# mainboard.net
KiCad netlist of a schematic drawn in EAGLE
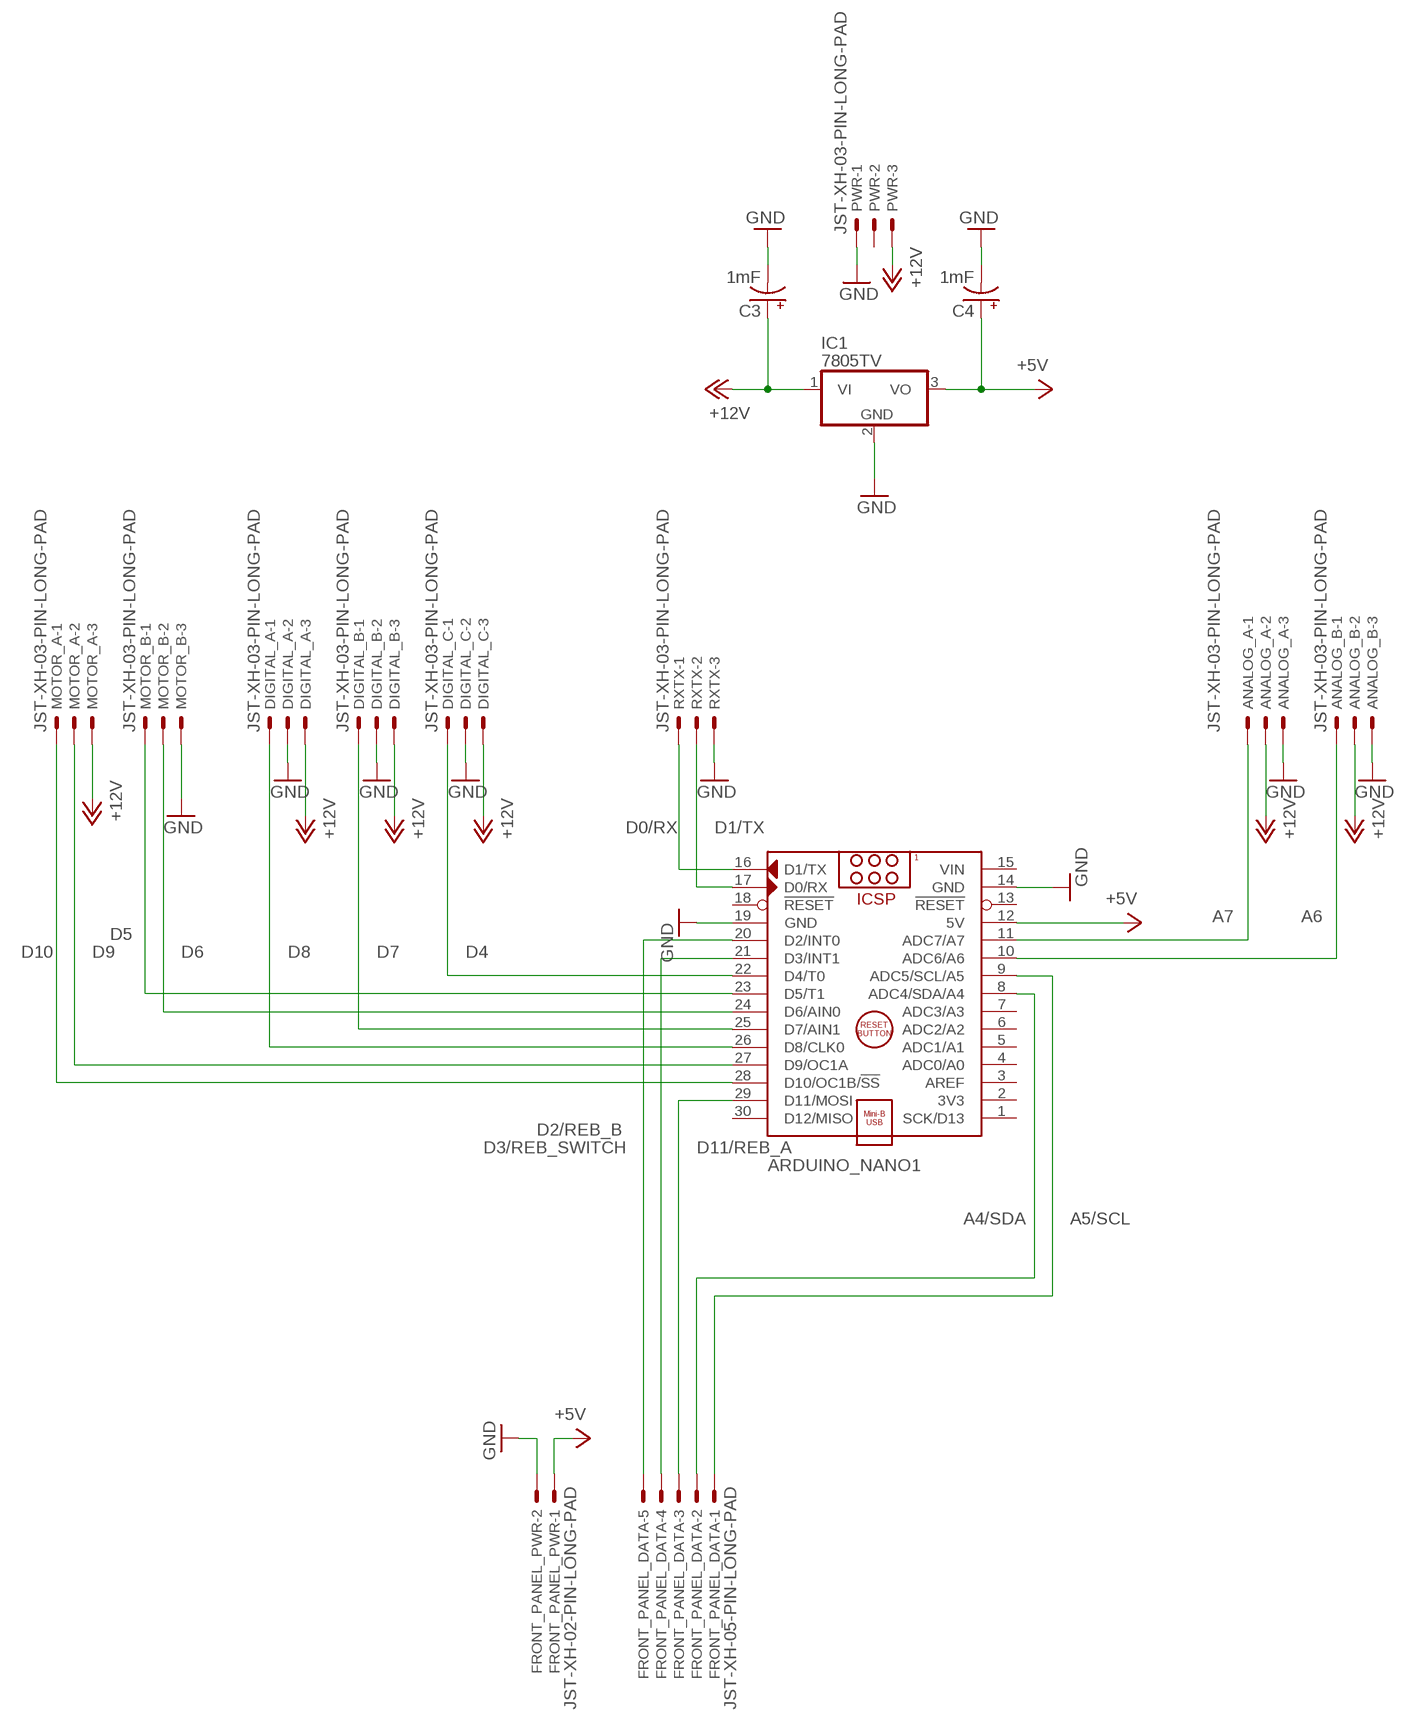
[diagram p0: schematic, sheet 1]

(export (version "E")
  (design (tool "Eeschema 10.0.6"))
  (components
    (comp (ref "ANALOG_A")
      (value "JST-XH-03-PIN-LONG-PAD")
      (footprint "eagle-import:JST-XH-03-PACKAGE-LONG-PAD")
      (libsource (lib "eagle-import") (part "JST-XH-03-PIN-LONG-PAD"))
    )
    (comp (ref "ANALOG_B")
      (value "JST-XH-03-PIN-LONG-PAD")
      (footprint "eagle-import:JST-XH-03-PACKAGE-LONG-PAD")
      (libsource (lib "eagle-import") (part "JST-XH-03-PIN-LONG-PAD"))
    )
    (comp (ref "ARDUINO_NANO1")
      (value "ARDUINO_NANO")
      (footprint "eagle-import:ARDUINO_NANO")
      (libsource (lib "eagle-import") (part "ARDUINO_NANO"))
    )
    (comp (ref "C3")
      (value "1mF")
      (footprint "eagle-import:CPOL-RADIAL-5MM-10MM")
      (libsource (lib "eagle-import") (part "1000UF-RADIAL-5MM-25V-20%"))
    )
    (comp (ref "C4")
      (value "1mF")
      (footprint "eagle-import:CPOL-RADIAL-5MM-10MM")
      (libsource (lib "eagle-import") (part "1000UF-RADIAL-5MM-25V-20%"))
    )
    (comp (ref "DIGITAL_A")
      (value "JST-XH-03-PIN-LONG-PAD")
      (footprint "eagle-import:JST-XH-03-PACKAGE-LONG-PAD")
      (libsource (lib "eagle-import") (part "JST-XH-03-PIN-LONG-PAD"))
    )
    (comp (ref "DIGITAL_B")
      (value "JST-XH-03-PIN-LONG-PAD")
      (footprint "eagle-import:JST-XH-03-PACKAGE-LONG-PAD")
      (libsource (lib "eagle-import") (part "JST-XH-03-PIN-LONG-PAD"))
    )
    (comp (ref "DIGITAL_C")
      (value "JST-XH-03-PIN-LONG-PAD")
      (footprint "eagle-import:JST-XH-03-PACKAGE-LONG-PAD")
      (libsource (lib "eagle-import") (part "JST-XH-03-PIN-LONG-PAD"))
    )
    (comp (ref "FRONT_PANEL_DATA")
      (value "JST-XH-05-PIN-LONG-PAD")
      (footprint "eagle-import:JST-XH-05-PACKAGE-LONG-PAD")
      (libsource (lib "eagle-import") (part "JST-XH-05-PIN-LONG-PAD"))
    )
    (comp (ref "FRONT_PANEL_PWR")
      (value "JST-XH-02-PIN-LONG-PAD")
      (footprint "eagle-import:JST-XH-02-PACKAGE-LONG-PAD")
      (libsource (lib "eagle-import") (part "JST-XH-02-PIN-LONG-PAD"))
    )
    (comp (ref "IC1")
      (value "7805TV")
      (footprint "eagle-import:TO220V")
      (libsource (lib "eagle-import") (part "78TV05"))
    )
    (comp (ref "MOTOR_A")
      (value "JST-XH-03-PIN-LONG-PAD")
      (footprint "eagle-import:JST-XH-03-PACKAGE-LONG-PAD")
      (libsource (lib "eagle-import") (part "JST-XH-03-PIN-LONG-PAD"))
    )
    (comp (ref "MOTOR_B")
      (value "JST-XH-03-PIN-LONG-PAD")
      (footprint "eagle-import:JST-XH-03-PACKAGE-LONG-PAD")
      (libsource (lib "eagle-import") (part "JST-XH-03-PIN-LONG-PAD"))
    )
    (comp (ref "PWR")
      (value "JST-XH-03-PIN-LONG-PAD")
      (footprint "eagle-import:JST-XH-03-PACKAGE-LONG-PAD")
      (libsource (lib "eagle-import") (part "JST-XH-03-PIN-LONG-PAD"))
    )
    (comp (ref "RXTX")
      (value "JST-XH-03-PIN-LONG-PAD")
      (footprint "eagle-import:JST-XH-03-PACKAGE-LONG-PAD")
      (libsource (lib "eagle-import") (part "JST-XH-03-PIN-LONG-PAD"))
    )
  )
  (nets
    (net (code "1") (name "+5V") (class "Default")
      (node (ref "ARDUINO_NANO1") (pin "12") (pinfunction "5V_12") (pintype "power_in"))
      (node (ref "C4") (pin "+") (pinfunction "+_+") (pintype "passive"))
      (node (ref "FRONT_PANEL_PWR") (pin "1") (pinfunction "S_1") (pintype "passive"))
      (node (ref "IC1") (pin "3") (pinfunction "VO_3") (pintype "passive"))
    )
    (net (code "2") (name "+12V") (class "Default")
      (node (ref "ANALOG_A") (pin "2") (pinfunction "S_2") (pintype "passive"))
      (node (ref "ANALOG_B") (pin "2") (pinfunction "S_2") (pintype "passive"))
      (node (ref "C3") (pin "+") (pinfunction "+_+") (pintype "passive"))
      (node (ref "DIGITAL_A") (pin "3") (pinfunction "S_3") (pintype "passive"))
      (node (ref "DIGITAL_B") (pin "3") (pinfunction "S_3") (pintype "passive"))
      (node (ref "DIGITAL_C") (pin "3") (pinfunction "S_3") (pintype "passive"))
      (node (ref "IC1") (pin "1") (pinfunction "VI_1") (pintype "input"))
      (node (ref "MOTOR_A") (pin "3") (pinfunction "S_3") (pintype "passive"))
      (node (ref "PWR") (pin "3") (pinfunction "S_3") (pintype "passive"))
    )
    (net (code "3") (name "/A4{slash}SDA") (class "Default")
      (node (ref "ARDUINO_NANO1") (pin "8") (pinfunction "ADC4/SDA/A4_8") (pintype "bidirectional"))
      (node (ref "FRONT_PANEL_DATA") (pin "2") (pinfunction "S_2") (pintype "passive"))
    )
    (net (code "4") (name "/A5{slash}SCL") (class "Default")
      (node (ref "ARDUINO_NANO1") (pin "9") (pinfunction "ADC5/SCL/A5_9") (pintype "bidirectional"))
      (node (ref "FRONT_PANEL_DATA") (pin "1") (pinfunction "S_1") (pintype "passive"))
    )
    (net (code "5") (name "/A6") (class "Default")
      (node (ref "ANALOG_B") (pin "1") (pinfunction "S_1") (pintype "passive"))
      (node (ref "ARDUINO_NANO1") (pin "10") (pinfunction "ADC6/A6_10") (pintype "bidirectional"))
    )
    (net (code "6") (name "/A7") (class "Default")
      (node (ref "ANALOG_A") (pin "1") (pinfunction "S_1") (pintype "passive"))
      (node (ref "ARDUINO_NANO1") (pin "11") (pinfunction "ADC7/A7_11") (pintype "bidirectional"))
    )
    (net (code "7") (name "/D0{slash}RX") (class "Default")
      (node (ref "ARDUINO_NANO1") (pin "17") (pinfunction "D0/RX_17") (pintype "bidirectional"))
      (node (ref "RXTX") (pin "2") (pinfunction "S_2") (pintype "passive"))
    )
    (net (code "8") (name "/D1{slash}TX") (class "Default")
      (node (ref "ARDUINO_NANO1") (pin "16") (pinfunction "D1/TX_16") (pintype "bidirectional"))
      (node (ref "RXTX") (pin "1") (pinfunction "S_1") (pintype "passive"))
    )
    (net (code "9") (name "/D2{slash}REB_B") (class "Default")
      (node (ref "ARDUINO_NANO1") (pin "20") (pinfunction "D2/INT0_20") (pintype "bidirectional"))
      (node (ref "FRONT_PANEL_DATA") (pin "5") (pinfunction "S_5") (pintype "passive"))
    )
    (net (code "10") (name "/D3{slash}REB_SWITCH") (class "Default")
      (node (ref "ARDUINO_NANO1") (pin "21") (pinfunction "D3/INT1_21") (pintype "bidirectional"))
      (node (ref "FRONT_PANEL_DATA") (pin "4") (pinfunction "S_4") (pintype "passive"))
    )
    (net (code "11") (name "/D4") (class "Default")
      (node (ref "ARDUINO_NANO1") (pin "22") (pinfunction "D4/T0_22") (pintype "bidirectional"))
      (node (ref "DIGITAL_C") (pin "1") (pinfunction "S_1") (pintype "passive"))
    )
    (net (code "12") (name "/D5") (class "Default")
      (node (ref "ARDUINO_NANO1") (pin "23") (pinfunction "D5/T1_23") (pintype "bidirectional"))
      (node (ref "MOTOR_B") (pin "1") (pinfunction "S_1") (pintype "passive"))
    )
    (net (code "13") (name "/D6") (class "Default")
      (node (ref "ARDUINO_NANO1") (pin "24") (pinfunction "D6/AIN0_24") (pintype "bidirectional"))
      (node (ref "MOTOR_B") (pin "2") (pinfunction "S_2") (pintype "passive"))
    )
    (net (code "14") (name "/D7") (class "Default")
      (node (ref "ARDUINO_NANO1") (pin "25") (pinfunction "D7/AIN1_25") (pintype "bidirectional"))
      (node (ref "DIGITAL_B") (pin "1") (pinfunction "S_1") (pintype "passive"))
    )
    (net (code "15") (name "/D8") (class "Default")
      (node (ref "ARDUINO_NANO1") (pin "26") (pinfunction "D8/CLK0_26") (pintype "bidirectional"))
      (node (ref "DIGITAL_A") (pin "1") (pinfunction "S_1") (pintype "passive"))
    )
    (net (code "16") (name "/D9") (class "Default")
      (node (ref "ARDUINO_NANO1") (pin "27") (pinfunction "D9/OC1A_27") (pintype "bidirectional"))
      (node (ref "MOTOR_A") (pin "2") (pinfunction "S_2") (pintype "passive"))
    )
    (net (code "17") (name "/D10") (class "Default")
      (node (ref "ARDUINO_NANO1") (pin "28") (pinfunction "D10/OC1B/~{SS}_28") (pintype "bidirectional"))
      (node (ref "MOTOR_A") (pin "1") (pinfunction "S_1") (pintype "passive"))
    )
    (net (code "18") (name "/D11{slash}REB_A") (class "Default")
      (node (ref "ARDUINO_NANO1") (pin "29") (pinfunction "D11/MOSI_29") (pintype "bidirectional"))
      (node (ref "FRONT_PANEL_DATA") (pin "3") (pinfunction "S_3") (pintype "passive"))
    )
    (net (code "19") (name "/VIN") (class "Default")
      (node (ref "ARDUINO_NANO1") (pin "15") (pinfunction "VIN_15") (pintype "power_in"))
    )
    (net (code "20") (name "GND") (class "Default")
      (node (ref "ANALOG_A") (pin "3") (pinfunction "S_3") (pintype "passive"))
      (node (ref "ANALOG_B") (pin "3") (pinfunction "S_3") (pintype "passive"))
      (node (ref "ARDUINO_NANO1") (pin "14") (pinfunction "GND_14") (pintype "power_in"))
      (node (ref "ARDUINO_NANO1") (pin "19") (pinfunction "GND_19") (pintype "power_in"))
      (node (ref "C3") (pin "-") (pinfunction "-_-") (pintype "passive"))
      (node (ref "C4") (pin "-") (pinfunction "-_-") (pintype "passive"))
      (node (ref "DIGITAL_A") (pin "2") (pinfunction "S_2") (pintype "passive"))
      (node (ref "DIGITAL_B") (pin "2") (pinfunction "S_2") (pintype "passive"))
      (node (ref "DIGITAL_C") (pin "2") (pinfunction "S_2") (pintype "passive"))
      (node (ref "FRONT_PANEL_PWR") (pin "2") (pinfunction "S_2") (pintype "passive"))
      (node (ref "IC1") (pin "2") (pinfunction "GND_2") (pintype "passive"))
      (node (ref "MOTOR_B") (pin "3") (pinfunction "S_3") (pintype "passive"))
      (node (ref "PWR") (pin "1") (pinfunction "S_1") (pintype "passive"))
      (node (ref "RXTX") (pin "3") (pinfunction "S_3") (pintype "passive"))
    )
    (net (code "21") (name "unconnected-(ARDUINO_NANO1-3V3-Pad2)") (class "Default")
      (node (ref "ARDUINO_NANO1") (pin "2") (pinfunction "3V3_2") (pintype "output"))
    )
    (net (code "22") (name "unconnected-(ARDUINO_NANO1-ADC0{slash}A0-Pad4)") (class "Default")
      (node (ref "ARDUINO_NANO1") (pin "4") (pinfunction "ADC0/A0_4") (pintype "bidirectional"))
    )
    (net (code "23") (name "unconnected-(ARDUINO_NANO1-ADC1{slash}A1-Pad5)") (class "Default")
      (node (ref "ARDUINO_NANO1") (pin "5") (pinfunction "ADC1/A1_5") (pintype "bidirectional"))
    )
    (net (code "24") (name "unconnected-(ARDUINO_NANO1-ADC2{slash}A2-Pad6)") (class "Default")
      (node (ref "ARDUINO_NANO1") (pin "6") (pinfunction "ADC2/A2_6") (pintype "bidirectional"))
    )
    (net (code "25") (name "unconnected-(ARDUINO_NANO1-ADC3{slash}A3-Pad7)") (class "Default")
      (node (ref "ARDUINO_NANO1") (pin "7") (pinfunction "ADC3/A3_7") (pintype "bidirectional"))
    )
    (net (code "26") (name "unconnected-(ARDUINO_NANO1-AREF-Pad3)") (class "Default")
      (node (ref "ARDUINO_NANO1") (pin "3") (pinfunction "AREF_3") (pintype "input"))
    )
    (net (code "27") (name "unconnected-(ARDUINO_NANO1-D12{slash}MISO-Pad30)") (class "Default")
      (node (ref "ARDUINO_NANO1") (pin "30") (pinfunction "D12/MISO_30") (pintype "bidirectional"))
    )
    (net (code "28") (name "unconnected-(ARDUINO_NANO1-SCK{slash}D13-Pad1)") (class "Default")
      (node (ref "ARDUINO_NANO1") (pin "1") (pinfunction "SCK/D13_1") (pintype "bidirectional"))
    )
    (net (code "29") (name "unconnected-(ARDUINO_NANO1-~{RESET}-Pad13)") (class "Default")
      (node (ref "ARDUINO_NANO1") (pin "13") (pinfunction "~{RESET}_13") (pintype "input"))
    )
    (net (code "30") (name "unconnected-(ARDUINO_NANO1-~{RESET}-Pad18)") (class "Default")
      (node (ref "ARDUINO_NANO1") (pin "18") (pinfunction "~{RESET}_18") (pintype "input"))
    )
    (net (code "31") (name "unconnected-(PWRB-S-Pad2)") (class "Default")
      (node (ref "PWR") (pin "2") (pinfunction "S_2") (pintype "passive"))
    )
  )
)
